# Armor_Plate.net
KiCad netlist of a schematic drawn in Altium Designer
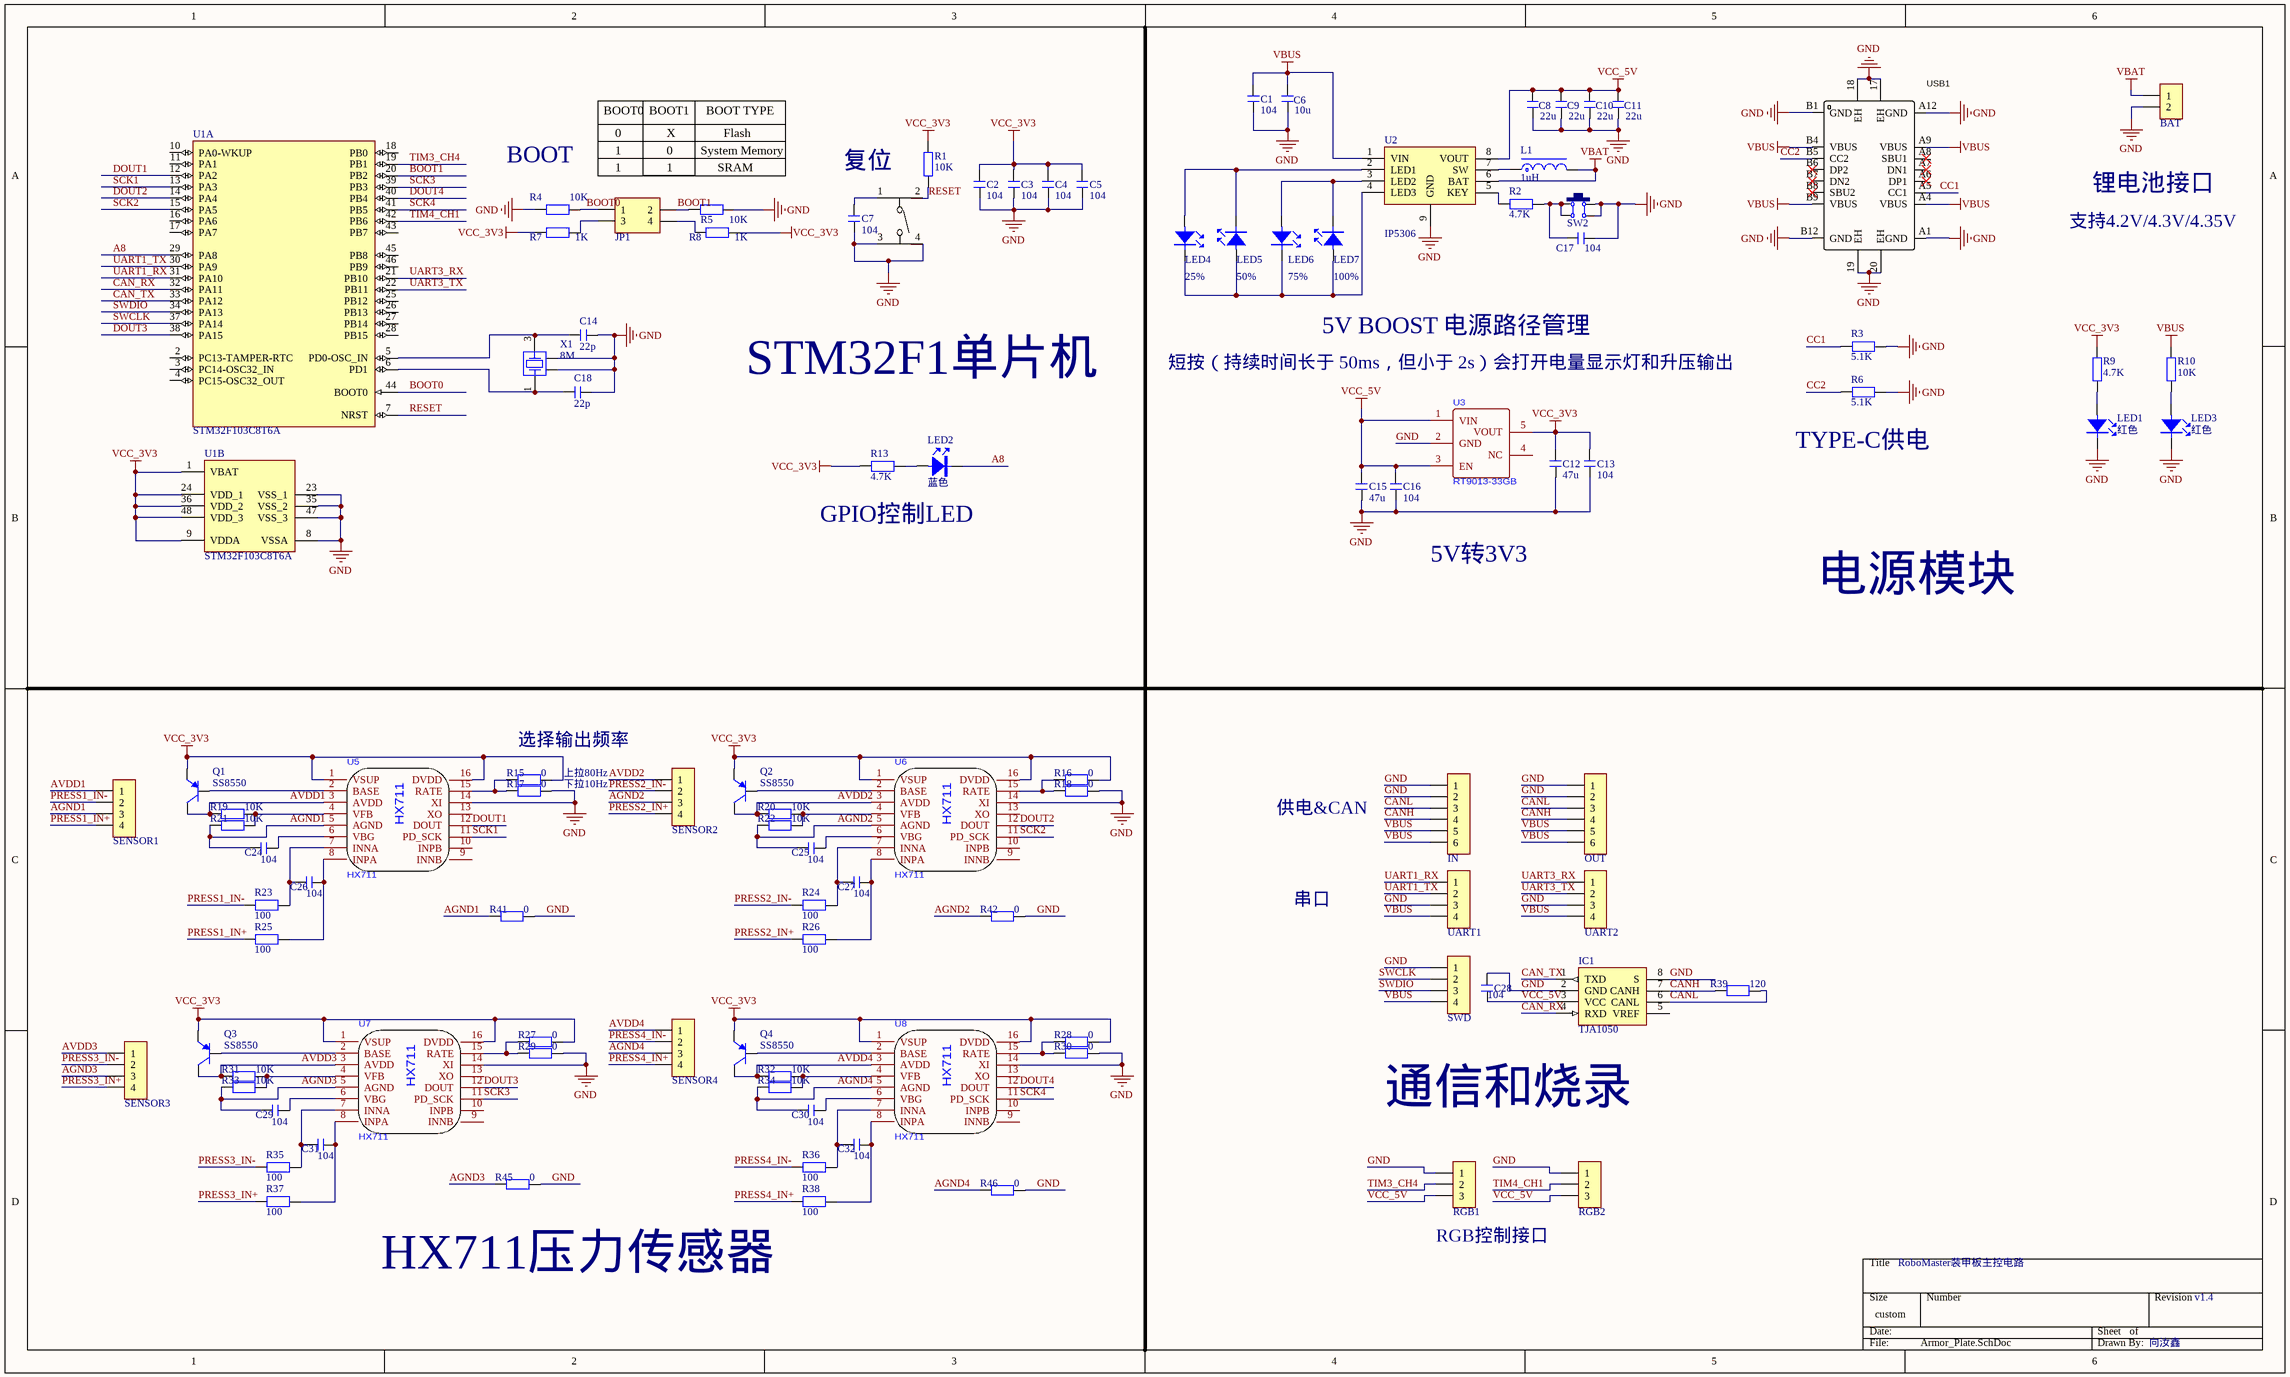
[diagram p0: Armor_Plate.SchDoc]

(export (version "E")
  (design (tool "Eeschema 10.0.6"))
  (components
    (comp (ref "BAT")
      (value "HDR-1X2")
      (footprint "XH2.54-WS-2P")
      (description "2P接插件")
      (libsource (lib "18 - 接插件-脚距2.54mm (100mil) ") (part "Header 2"))
    )
    (comp (ref "C1")
      (value "104")
      (footprint "C 0603_L")
      (description "贴片电容")
      (libsource (lib "01 - 电容-电阻-电感") (part "C"))
    )
    (comp (ref "C2")
      (value "104")
      (footprint "C 0603_L")
      (description "贴片电容")
      (libsource (lib "01 - 电容-电阻-电感") (part "C"))
    )
    (comp (ref "C3")
      (value "104")
      (footprint "C 0603_L")
      (description "贴片电容")
      (libsource (lib "01 - 电容-电阻-电感") (part "C"))
    )
    (comp (ref "C4")
      (value "104")
      (footprint "C 0603_L")
      (description "贴片电容")
      (libsource (lib "01 - 电容-电阻-电感") (part "C"))
    )
    (comp (ref "C5")
      (value "104")
      (footprint "C 0603_L")
      (description "贴片电容")
      (libsource (lib "01 - 电容-电阻-电感") (part "C"))
    )
    (comp (ref "C6")
      (value "10u")
      (footprint "C 0603_L")
      (description "贴片电容")
      (libsource (lib "01 - 电容-电阻-电感") (part "C"))
    )
    (comp (ref "C7")
      (value "104")
      (footprint "C 0603_L")
      (description "贴片电容")
      (libsource (lib "01 - 电容-电阻-电感") (part "C"))
    )
    (comp (ref "C8")
      (value "22u")
      (footprint "C 0603_L")
      (description "贴片电容")
      (libsource (lib "01 - 电容-电阻-电感") (part "C"))
    )
    (comp (ref "C9")
      (value "22u")
      (footprint "C 0603_L")
      (description "贴片电容")
      (libsource (lib "01 - 电容-电阻-电感") (part "C"))
    )
    (comp (ref "C10")
      (value "22u")
      (footprint "C 0603_L")
      (description "贴片电容")
      (libsource (lib "01 - 电容-电阻-电感") (part "C"))
    )
    (comp (ref "C11")
      (value "22u")
      (footprint "C 0603_L")
      (description "贴片电容")
      (libsource (lib "01 - 电容-电阻-电感") (part "C"))
    )
    (comp (ref "C12")
      (value "47u")
      (footprint "C 0805_L")
      (description "贴片电容")
      (libsource (lib "01 - 电容-电阻-电感") (part "C"))
    )
    (comp (ref "C13")
      (value "104")
      (footprint "C 0805_L")
      (description "贴片电容")
      (libsource (lib "01 - 电容-电阻-电感") (part "C"))
    )
    (comp (ref "C14")
      (value "22p")
      (footprint "C 0603_L")
      (description "贴片电容")
      (libsource (lib "01 - 电容-电阻-电感") (part "C"))
    )
    (comp (ref "C15")
      (value "47u")
      (footprint "C 0805_L")
      (description "贴片电容")
      (libsource (lib "01 - 电容-电阻-电感") (part "C"))
    )
    (comp (ref "C16")
      (value "104")
      (footprint "C 0805_L")
      (description "贴片电容")
      (libsource (lib "01 - 电容-电阻-电感") (part "C"))
    )
    (comp (ref "C17")
      (value "104")
      (footprint "C 0603_L")
      (description "贴片电容")
      (libsource (lib "01 - 电容-电阻-电感") (part "C"))
    )
    (comp (ref "C18")
      (value "22p")
      (footprint "C 0603_L")
      (description "贴片电容")
      (libsource (lib "01 - 电容-电阻-电感") (part "C"))
    )
    (comp (ref "C24")
      (value "104")
      (footprint "C 0603_L")
      (description "贴片电容")
      (libsource (lib "01 - 电容-电阻-电感") (part "C"))
    )
    (comp (ref "C25")
      (value "104")
      (footprint "C 0603_L")
      (description "贴片电容")
      (libsource (lib "01 - 电容-电阻-电感") (part "C"))
    )
    (comp (ref "C26")
      (value "104")
      (footprint "C 0603_L")
      (description "贴片电容")
      (libsource (lib "01 - 电容-电阻-电感") (part "C"))
    )
    (comp (ref "C27")
      (value "104")
      (footprint "C 0603_L")
      (description "贴片电容")
      (libsource (lib "01 - 电容-电阻-电感") (part "C"))
    )
    (comp (ref "C28")
      (value "104")
      (footprint "C 0603_L")
      (description "贴片电容")
      (libsource (lib "01 - 电容-电阻-电感") (part "C"))
    )
    (comp (ref "C29")
      (value "104")
      (footprint "C 0603_L")
      (description "贴片电容")
      (libsource (lib "01 - 电容-电阻-电感") (part "C"))
    )
    (comp (ref "C30")
      (value "104")
      (footprint "C 0603_L")
      (description "贴片电容")
      (libsource (lib "01 - 电容-电阻-电感") (part "C"))
    )
    (comp (ref "C31")
      (value "104")
      (footprint "C 0603_L")
      (description "贴片电容")
      (libsource (lib "01 - 电容-电阻-电感") (part "C"))
    )
    (comp (ref "C32")
      (value "104")
      (footprint "C 0603_L")
      (description "贴片电容")
      (libsource (lib "01 - 电容-电阻-电感") (part "C"))
    )
    (comp (ref "IC1")
      (value "TJA1050")
      (footprint "SOP8_N")
      (description "CAN总线收发芯片")
      (libsource (lib "39 - 其他芯片类") (part "TJA1050"))
    )
    (comp (ref "IN")
      (value "HDR-1X6")
      (footprint "GH1.25-WS-6P")
      (description "6P接插件")
      (libsource (lib "14 - 接插件-脚距1.25mm") (part "Header 6"))
    )
    (comp (ref "JP1")
      (value "Header2X2")
      (footprint "HDR2.54-LI-2x2P")
      (description "2*2P接插件")
      (libsource (lib "18 - 接插件-脚距2.54mm (100mil) ") (part "Header 2X2"))
    )
    (comp (ref "L1")
      (value "1uH")
      (footprint "CD31")
      (description "CD系列贴片线绕功率电感")
      (libsource (lib "01 - 电容-电阻-电感") (part "L-SMD"))
    )
    (comp (ref "LED1")
      (value "红色")
      (footprint "LED 0805R")
      (description "贴片LED")
      (libsource (lib "02 - 二极管(LED)-三极管-整流桥") (part "LED-SMD"))
    )
    (comp (ref "LED2")
      (value "蓝色")
      (footprint "LED 0805B")
      (description "贴片LED")
      (libsource (lib "02 - 二极管(LED)-三极管-整流桥") (part "LED-SMD"))
    )
    (comp (ref "LED3")
      (value "红色")
      (footprint "LED 0805R")
      (description "贴片LED")
      (libsource (lib "02 - 二极管(LED)-三极管-整流桥") (part "LED-SMD"))
    )
    (comp (ref "LED4")
      (value "25%")
      (footprint "LED 0603G")
      (description "贴片LED")
      (libsource (lib "02 - 二极管(LED)-三极管-整流桥") (part "LED-SMD"))
    )
    (comp (ref "LED5")
      (value "50%")
      (footprint "LED 0603G")
      (description "贴片LED")
      (libsource (lib "02 - 二极管(LED)-三极管-整流桥") (part "LED-SMD"))
    )
    (comp (ref "LED6")
      (value "75%")
      (footprint "LED 0603G")
      (description "贴片LED")
      (libsource (lib "02 - 二极管(LED)-三极管-整流桥") (part "LED-SMD"))
    )
    (comp (ref "LED7")
      (value "100%")
      (footprint "LED 0603G")
      (description "贴片LED")
      (libsource (lib "02 - 二极管(LED)-三极管-整流桥") (part "LED-SMD"))
    )
    (comp (ref "OUT")
      (value "HDR-1X6")
      (footprint "GH1.25-WS-6P")
      (description "6P接插件")
      (libsource (lib "14 - 接插件-脚距1.25mm") (part "Header 6"))
    )
    (comp (ref "Q1")
      (value "SS8550")
      (footprint "SOT23-3N")
      (description "高频放大-PNP型")
      (libsource (lib "02 - 二极管(LED)-三极管-整流桥") (part "8550-SMD"))
    )
    (comp (ref "Q2")
      (value "SS8550")
      (footprint "SOT23-3N")
      (description "高频放大-PNP型")
      (libsource (lib "02 - 二极管(LED)-三极管-整流桥") (part "8550-SMD"))
    )
    (comp (ref "Q3")
      (value "SS8550")
      (footprint "SOT23-3N")
      (description "高频放大-PNP型")
      (libsource (lib "02 - 二极管(LED)-三极管-整流桥") (part "8550-SMD"))
    )
    (comp (ref "Q4")
      (value "SS8550")
      (footprint "SOT23-3N")
      (description "高频放大-PNP型")
      (libsource (lib "02 - 二极管(LED)-三极管-整流桥") (part "8550-SMD"))
    )
    (comp (ref "R1")
      (value "10K")
      (footprint "R 0603_L")
      (description "贴片电阻")
      (libsource (lib "01 - 电容-电阻-电感") (part "R"))
    )
    (comp (ref "R2")
      (value "4.7K")
      (footprint "R 0603_L")
      (description "贴片电阻")
      (libsource (lib "01 - 电容-电阻-电感") (part "R"))
    )
    (comp (ref "R3")
      (value "5.1K")
      (footprint "R 0603_L")
      (description "贴片电阻")
      (libsource (lib "01 - 电容-电阻-电感") (part "R"))
    )
    (comp (ref "R4")
      (value "10K")
      (footprint "R 0603_L")
      (description "贴片电阻")
      (libsource (lib "01 - 电容-电阻-电感") (part "R"))
    )
    (comp (ref "R5")
      (value "10K")
      (footprint "R 0603_L")
      (description "贴片电阻")
      (libsource (lib "01 - 电容-电阻-电感") (part "R"))
    )
    (comp (ref "R6")
      (value "5.1K")
      (footprint "R 0603_L")
      (description "贴片电阻")
      (libsource (lib "01 - 电容-电阻-电感") (part "R"))
    )
    (comp (ref "R7")
      (value "1K")
      (footprint "R 0603_L")
      (description "贴片电阻")
      (libsource (lib "01 - 电容-电阻-电感") (part "R"))
    )
    (comp (ref "R8")
      (value "1K")
      (footprint "R 0603_L")
      (description "贴片电阻")
      (libsource (lib "01 - 电容-电阻-电感") (part "R"))
    )
    (comp (ref "R9")
      (value "4.7K")
      (footprint "R 0603_L")
      (description "贴片电阻")
      (libsource (lib "01 - 电容-电阻-电感") (part "R"))
    )
    (comp (ref "R10")
      (value "10K")
      (footprint "R 0603_L")
      (description "贴片电阻")
      (libsource (lib "01 - 电容-电阻-电感") (part "R"))
    )
    (comp (ref "R13")
      (value "4.7K")
      (footprint "R 0603_L")
      (description "贴片电阻")
      (libsource (lib "01 - 电容-电阻-电感") (part "R"))
    )
    (comp (ref "R15")
      (value "0")
      (footprint "R 0603_L")
      (description "贴片电阻")
      (libsource (lib "01 - 电容-电阻-电感") (part "R"))
    )
    (comp (ref "R16")
      (value "0")
      (footprint "R 0603_L")
      (description "贴片电阻")
      (libsource (lib "01 - 电容-电阻-电感") (part "R"))
    )
    (comp (ref "R17")
      (value "0")
      (footprint "R 0603_L")
      (description "贴片电阻")
      (libsource (lib "01 - 电容-电阻-电感") (part "R"))
    )
    (comp (ref "R18")
      (value "0")
      (footprint "R 0603_L")
      (description "贴片电阻")
      (libsource (lib "01 - 电容-电阻-电感") (part "R"))
    )
    (comp (ref "R19")
      (value "10K")
      (footprint "R 0603_L")
      (description "贴片电阻")
      (libsource (lib "01 - 电容-电阻-电感") (part "R"))
    )
    (comp (ref "R20")
      (value "10K")
      (footprint "R 0603_L")
      (description "贴片电阻")
      (libsource (lib "01 - 电容-电阻-电感") (part "R"))
    )
    (comp (ref "R21")
      (value "10K")
      (footprint "R 0603_L")
      (description "贴片电阻")
      (libsource (lib "01 - 电容-电阻-电感") (part "R"))
    )
    (comp (ref "R22")
      (value "10K")
      (footprint "R 0603_L")
      (description "贴片电阻")
      (libsource (lib "01 - 电容-电阻-电感") (part "R"))
    )
    (comp (ref "R23")
      (value "100")
      (footprint "R 0603_L")
      (description "贴片电阻")
      (libsource (lib "01 - 电容-电阻-电感") (part "R"))
    )
    (comp (ref "R24")
      (value "100")
      (footprint "R 0603_L")
      (description "贴片电阻")
      (libsource (lib "01 - 电容-电阻-电感") (part "R"))
    )
    (comp (ref "R25")
      (value "100")
      (footprint "R 0603_L")
      (description "贴片电阻")
      (libsource (lib "01 - 电容-电阻-电感") (part "R"))
    )
    (comp (ref "R26")
      (value "100")
      (footprint "R 0603_L")
      (description "贴片电阻")
      (libsource (lib "01 - 电容-电阻-电感") (part "R"))
    )
    (comp (ref "R27")
      (value "0")
      (footprint "R 0603_L")
      (description "贴片电阻")
      (libsource (lib "01 - 电容-电阻-电感") (part "R"))
    )
    (comp (ref "R28")
      (value "0")
      (footprint "R 0603_L")
      (description "贴片电阻")
      (libsource (lib "01 - 电容-电阻-电感") (part "R"))
    )
    (comp (ref "R29")
      (value "0")
      (footprint "R 0603_L")
      (description "贴片电阻")
      (libsource (lib "01 - 电容-电阻-电感") (part "R"))
    )
    (comp (ref "R30")
      (value "0")
      (footprint "R 0603_L")
      (description "贴片电阻")
      (libsource (lib "01 - 电容-电阻-电感") (part "R"))
    )
    (comp (ref "R31")
      (value "10K")
      (footprint "R 0603_L")
      (description "贴片电阻")
      (libsource (lib "01 - 电容-电阻-电感") (part "R"))
    )
    (comp (ref "R32")
      (value "10K")
      (footprint "R 0603_L")
      (description "贴片电阻")
      (libsource (lib "01 - 电容-电阻-电感") (part "R"))
    )
    (comp (ref "R33")
      (value "10K")
      (footprint "R 0603_L")
      (description "贴片电阻")
      (libsource (lib "01 - 电容-电阻-电感") (part "R"))
    )
    (comp (ref "R34")
      (value "10K")
      (footprint "R 0603_L")
      (description "贴片电阻")
      (libsource (lib "01 - 电容-电阻-电感") (part "R"))
    )
    (comp (ref "R35")
      (value "100")
      (footprint "R 0603_L")
      (description "贴片电阻")
      (libsource (lib "01 - 电容-电阻-电感") (part "R"))
    )
    (comp (ref "R36")
      (value "100")
      (footprint "R 0603_L")
      (description "贴片电阻")
      (libsource (lib "01 - 电容-电阻-电感") (part "R"))
    )
    (comp (ref "R37")
      (value "100")
      (footprint "R 0603_L")
      (description "贴片电阻")
      (libsource (lib "01 - 电容-电阻-电感") (part "R"))
    )
    (comp (ref "R38")
      (value "100")
      (footprint "R 0603_L")
      (description "贴片电阻")
      (libsource (lib "01 - 电容-电阻-电感") (part "R"))
    )
    (comp (ref "R39")
      (value "120")
      (footprint "R 0603_L")
      (description "贴片电阻")
      (libsource (lib "01 - 电容-电阻-电感") (part "R"))
    )
    (comp (ref "R41")
      (value "0")
      (footprint "R 0603_L")
      (description "贴片电阻")
      (libsource (lib "01 - 电容-电阻-电感") (part "R"))
    )
    (comp (ref "R42")
      (value "0")
      (footprint "R 0603_L")
      (description "贴片电阻")
      (libsource (lib "01 - 电容-电阻-电感") (part "R"))
    )
    (comp (ref "R45")
      (value "0")
      (footprint "R 0603_L")
      (description "贴片电阻")
      (libsource (lib "01 - 电容-电阻-电感") (part "R"))
    )
    (comp (ref "R46")
      (value "0")
      (footprint "R 0603_L")
      (description "贴片电阻")
      (libsource (lib "01 - 电容-电阻-电感") (part "R"))
    )
    (comp (ref "RGB1")
      (value "HDR-1X3")
      (footprint "GH1.25-WS-3P")
      (description "3P接插件")
      (libsource (lib "14 - 接插件-脚距1.25mm") (part "Header 3"))
    )
    (comp (ref "RGB2")
      (value "HDR-1X3")
      (footprint "GH1.25-WS-3P")
      (description "3P接插件")
      (libsource (lib "14 - 接插件-脚距1.25mm") (part "Header 3"))
    )
    (comp (ref "SENSOR1")
      (value "HDR-1X4")
      (footprint "GH1.25-WS-4P")
      (description "4P接插件")
      (libsource (lib "14 - 接插件-脚距1.25mm") (part "Header 4"))
    )
    (comp (ref "SENSOR2")
      (value "HDR-1X4")
      (footprint "GH1.25-WS-4P")
      (description "4P接插件")
      (libsource (lib "14 - 接插件-脚距1.25mm") (part "Header 4"))
    )
    (comp (ref "SENSOR3")
      (value "HDR-1X4")
      (footprint "GH1.25-WS-4P")
      (description "4P接插件")
      (libsource (lib "14 - 接插件-脚距1.25mm") (part "Header 4"))
    )
    (comp (ref "SENSOR4")
      (value "HDR-1X4")
      (footprint "GH1.25-WS-4P")
      (description "4P接插件")
      (libsource (lib "14 - 接插件-脚距1.25mm") (part "Header 4"))
    )
    (comp (ref "SW1")
      (value "ST-1188")
      (footprint "SW-SMD_4P-L4.2-W3.2-P2.15-LS5.2")
      (fields (field (name "MANUFACTURER") "RISHENG(日昇)"))
      (libsource (lib "My_SCHLIB") (part "SW-SMD_4P-L4.2-W3.2-P2.15-LS5.2"))
    )
    (comp (ref "SW2")
      (value "6x6x5")
      (footprint "TSW SMD-6*6*4.3")
      (description "贴片6x6轻触开关")
      (libsource (lib "03 - 按键-开关-晶振-蜂鸣器") (part "TSW SMD-6x6"))
    )
    (comp (ref "SWD")
      (value "HDR-1X4")
      (footprint "GH1.25-WS-4P")
      (description "4P接插件")
      (libsource (lib "14 - 接插件-脚距1.25mm") (part "Header 4"))
    )
    (comp (ref "U1")
      (value "STM32F103C8T6A")
      (footprint "LQFP48 7X7_N")
      (libsource (lib "28 - STM32系列单片机") (part "STM32F103C8T6"))
    )
    (comp (ref "U2")
      (value "IP5306")
      (footprint "SOP-8-EX")
      (description "移动电源IC")
      (libsource (lib "My_SCHLIB") (part "IP5306"))
    )
    (comp (ref "U3")
      (value "RT9013-33GB")
      (footprint "SOT-23-5_L3.0-W1.7-P0.95-LS2.8-BR")
      (libsource (lib "My_SCHLIB") (part "RT9013-33GB"))
    )
    (comp (ref "U5")
      (value "HX711")
      (footprint "SOP-16_L10.0-W3.9-P1.27-LS6.0-BL")
      (libsource (lib "My_SCHLIB") (part "HX711"))
    )
    (comp (ref "U6")
      (value "HX711")
      (footprint "SOP-16_L10.0-W3.9-P1.27-LS6.0-BL")
      (libsource (lib "My_SCHLIB") (part "HX711"))
    )
    (comp (ref "U7")
      (value "HX711")
      (footprint "SOP-16_L10.0-W3.9-P1.27-LS6.0-BL")
      (libsource (lib "My_SCHLIB") (part "HX711"))
    )
    (comp (ref "U8")
      (value "HX711")
      (footprint "SOP-16_L10.0-W3.9-P1.27-LS6.0-BL")
      (libsource (lib "My_SCHLIB") (part "HX711"))
    )
    (comp (ref "UART1")
      (value "HDR-1X4")
      (footprint "GH1.25-WS-4P")
      (description "4P接插件")
      (libsource (lib "14 - 接插件-脚距1.25mm") (part "Header 4"))
    )
    (comp (ref "UART2")
      (value "HDR-1X4")
      (footprint "GH1.25-WS-4P")
      (description "4P接插件")
      (libsource (lib "14 - 接插件-脚距1.25mm") (part "Header 4"))
    )
    (comp (ref "USB1")
      (value "~")
      (footprint "USB-C-SMD_KH-TYPE-C-16P")
      (description "USB")
      (fields
        (field (name "BOM_SUPPLIER PART") "C2798173")
        (field (name "BOM_MANUFACTURER PART") "TYPE-C-16M-005")
        (field (name "CONTRIBUTOR") "LCSC")
      )
      (libsource (lib "04 - 接口类-USB接口-网口") (part "TYPE-C-16M-005"))
    )
    (comp (ref "X1")
      (value "8M")
      (footprint "OSC 3225-4P")
      (description "4脚无源晶振")
      (libsource (lib "03 - 按键-开关-晶振-蜂鸣器") (part "XTAL-4P"))
    )
  )
  (nets
    (net (code "2") (name "/A8") (class "Default")
      (node (ref "LED2") (pin "2") (pinfunction "K_2") (pintype "passive"))
      (node (ref "U1") (pin "29") (pinfunction "PA8_29") (pintype "bidirectional"))
    )
    (net (code "3") (name "/AGND1") (class "Default")
      (node (ref "C24") (pin "2") (pinfunction "2_2") (pintype "passive"))
      (node (ref "R21") (pin "1") (pinfunction "1_1") (pintype "passive"))
      (node (ref "R41") (pin "1") (pinfunction "1_1") (pintype "passive"))
      (node (ref "SENSOR1") (pin "3") (pinfunction "3_3") (pintype "passive"))
      (node (ref "U5") (pin "5") (pinfunction "AGND_5") (pintype "passive"))
    )
    (net (code "4") (name "/AGND2") (class "Default")
      (node (ref "C25") (pin "2") (pinfunction "2_2") (pintype "passive"))
      (node (ref "R22") (pin "1") (pinfunction "1_1") (pintype "passive"))
      (node (ref "R42") (pin "1") (pinfunction "1_1") (pintype "passive"))
      (node (ref "SENSOR2") (pin "3") (pinfunction "3_3") (pintype "passive"))
      (node (ref "U6") (pin "5") (pinfunction "AGND_5") (pintype "passive"))
    )
    (net (code "5") (name "/AGND3") (class "Default")
      (node (ref "C29") (pin "2") (pinfunction "2_2") (pintype "passive"))
      (node (ref "R33") (pin "1") (pinfunction "1_1") (pintype "passive"))
      (node (ref "R45") (pin "1") (pinfunction "1_1") (pintype "passive"))
      (node (ref "SENSOR3") (pin "3") (pinfunction "3_3") (pintype "passive"))
      (node (ref "U7") (pin "5") (pinfunction "AGND_5") (pintype "passive"))
    )
    (net (code "6") (name "/AGND4") (class "Default")
      (node (ref "C30") (pin "2") (pinfunction "2_2") (pintype "passive"))
      (node (ref "R34") (pin "1") (pinfunction "1_1") (pintype "passive"))
      (node (ref "R46") (pin "1") (pinfunction "1_1") (pintype "passive"))
      (node (ref "SENSOR4") (pin "3") (pinfunction "3_3") (pintype "passive"))
      (node (ref "U8") (pin "5") (pinfunction "AGND_5") (pintype "passive"))
    )
    (net (code "7") (name "/AVDD1") (class "Default")
      (node (ref "Q1") (pin "3") (pinfunction "C_3") (pintype "passive"))
      (node (ref "R19") (pin "1") (pinfunction "1_1") (pintype "passive"))
      (node (ref "SENSOR1") (pin "1") (pinfunction "1_1") (pintype "passive"))
      (node (ref "U5") (pin "3") (pinfunction "AVDD_3") (pintype "passive"))
    )
    (net (code "8") (name "/AVDD2") (class "Default")
      (node (ref "Q2") (pin "3") (pinfunction "C_3") (pintype "passive"))
      (node (ref "R20") (pin "1") (pinfunction "1_1") (pintype "passive"))
      (node (ref "SENSOR2") (pin "1") (pinfunction "1_1") (pintype "passive"))
      (node (ref "U6") (pin "3") (pinfunction "AVDD_3") (pintype "passive"))
    )
    (net (code "9") (name "/AVDD3") (class "Default")
      (node (ref "Q3") (pin "3") (pinfunction "C_3") (pintype "passive"))
      (node (ref "R31") (pin "1") (pinfunction "1_1") (pintype "passive"))
      (node (ref "SENSOR3") (pin "1") (pinfunction "1_1") (pintype "passive"))
      (node (ref "U7") (pin "3") (pinfunction "AVDD_3") (pintype "passive"))
    )
    (net (code "10") (name "/AVDD4") (class "Default")
      (node (ref "Q4") (pin "3") (pinfunction "C_3") (pintype "passive"))
      (node (ref "R32") (pin "1") (pinfunction "1_1") (pintype "passive"))
      (node (ref "SENSOR4") (pin "1") (pinfunction "1_1") (pintype "passive"))
      (node (ref "U8") (pin "3") (pinfunction "AVDD_3") (pintype "passive"))
    )
    (net (code "11") (name "/BOOT0") (class "Default")
      (node (ref "JP1") (pin "1") (pinfunction "1_1") (pintype "passive"))
      (node (ref "R4") (pin "2") (pinfunction "2_2") (pintype "passive"))
      (node (ref "U1") (pin "44") (pinfunction "BOOT0_44") (pintype "input"))
    )
    (net (code "12") (name "/BOOT1") (class "Default")
      (node (ref "JP1") (pin "2") (pinfunction "2_2") (pintype "passive"))
      (node (ref "R5") (pin "1") (pinfunction "1_1") (pintype "passive"))
      (node (ref "U1") (pin "20") (pinfunction "PB2_20") (pintype "bidirectional"))
    )
    (net (code "13") (name "/CANH") (class "Default")
      (node (ref "IC1") (pin "7") (pinfunction "CANH_7") (pintype "passive"))
      (node (ref "IN") (pin "4") (pinfunction "4_4") (pintype "passive"))
      (node (ref "OUT") (pin "4") (pinfunction "4_4") (pintype "passive"))
      (node (ref "R39") (pin "1") (pinfunction "1_1") (pintype "passive"))
    )
    (net (code "14") (name "/CANL") (class "Default")
      (node (ref "IC1") (pin "6") (pinfunction "CANL_6") (pintype "passive"))
      (node (ref "IN") (pin "3") (pinfunction "3_3") (pintype "passive"))
      (node (ref "OUT") (pin "3") (pinfunction "3_3") (pintype "passive"))
      (node (ref "R39") (pin "2") (pinfunction "2_2") (pintype "passive"))
    )
    (net (code "15") (name "/CAN_RX") (class "Default")
      (node (ref "IC1") (pin "4") (pinfunction "RXD_4") (pintype "input"))
      (node (ref "U1") (pin "32") (pinfunction "PA11_32") (pintype "bidirectional"))
    )
    (net (code "16") (name "/CAN_TX") (class "Default")
      (node (ref "IC1") (pin "1") (pinfunction "TXD_1") (pintype "output"))
      (node (ref "U1") (pin "33") (pinfunction "PA12_33") (pintype "bidirectional"))
    )
    (net (code "17") (name "/CC1") (class "Default")
      (node (ref "R3") (pin "2") (pinfunction "2_2") (pintype "passive"))
      (node (ref "USB1") (pin "A5") (pinfunction "CC1_A5") (pintype "passive"))
    )
    (net (code "18") (name "/CC2") (class "Default")
      (node (ref "R6") (pin "2") (pinfunction "2_2") (pintype "passive"))
      (node (ref "USB1") (pin "B5") (pinfunction "CC2_B5") (pintype "passive"))
    )
    (net (code "19") (name "/DOUT1") (class "Default")
      (node (ref "U1") (pin "12") (pinfunction "PA2_12") (pintype "bidirectional"))
      (node (ref "U5") (pin "12") (pinfunction "DOUT_12") (pintype "passive"))
    )
    (net (code "20") (name "/DOUT2") (class "Default")
      (node (ref "U1") (pin "14") (pinfunction "PA4_14") (pintype "bidirectional"))
      (node (ref "U6") (pin "12") (pinfunction "DOUT_12") (pintype "passive"))
    )
    (net (code "21") (name "/DOUT3") (class "Default")
      (node (ref "U1") (pin "38") (pinfunction "PA15_38") (pintype "bidirectional"))
      (node (ref "U7") (pin "12") (pinfunction "DOUT_12") (pintype "passive"))
    )
    (net (code "22") (name "/DOUT4") (class "Default")
      (node (ref "U1") (pin "40") (pinfunction "PB4_40") (pintype "bidirectional"))
      (node (ref "U8") (pin "12") (pinfunction "DOUT_12") (pintype "passive"))
    )
    (net (code "23") (name "/PRESS1_IN+") (class "Default")
      (node (ref "R25") (pin "2") (pinfunction "2_2") (pintype "passive"))
      (node (ref "SENSOR1") (pin "4") (pinfunction "4_4") (pintype "passive"))
    )
    (net (code "24") (name "/PRESS1_IN-") (class "Default")
      (node (ref "R23") (pin "1") (pinfunction "1_1") (pintype "passive"))
      (node (ref "SENSOR1") (pin "2") (pinfunction "2_2") (pintype "passive"))
    )
    (net (code "25") (name "/PRESS2_IN+") (class "Default")
      (node (ref "R26") (pin "2") (pinfunction "2_2") (pintype "passive"))
      (node (ref "SENSOR2") (pin "4") (pinfunction "4_4") (pintype "passive"))
    )
    (net (code "26") (name "/PRESS2_IN-") (class "Default")
      (node (ref "R24") (pin "1") (pinfunction "1_1") (pintype "passive"))
      (node (ref "SENSOR2") (pin "2") (pinfunction "2_2") (pintype "passive"))
    )
    (net (code "27") (name "/PRESS3_IN+") (class "Default")
      (node (ref "R37") (pin "2") (pinfunction "2_2") (pintype "passive"))
      (node (ref "SENSOR3") (pin "4") (pinfunction "4_4") (pintype "passive"))
    )
    (net (code "28") (name "/PRESS3_IN-") (class "Default")
      (node (ref "R35") (pin "1") (pinfunction "1_1") (pintype "passive"))
      (node (ref "SENSOR3") (pin "2") (pinfunction "2_2") (pintype "passive"))
    )
    (net (code "29") (name "/PRESS4_IN+") (class "Default")
      (node (ref "R38") (pin "2") (pinfunction "2_2") (pintype "passive"))
      (node (ref "SENSOR4") (pin "4") (pinfunction "4_4") (pintype "passive"))
    )
    (net (code "30") (name "/PRESS4_IN-") (class "Default")
      (node (ref "R36") (pin "1") (pinfunction "1_1") (pintype "passive"))
      (node (ref "SENSOR4") (pin "2") (pinfunction "2_2") (pintype "passive"))
    )
    (net (code "31") (name "/RESET") (class "Default")
      (node (ref "R1") (pin "1") (pinfunction "1_1") (pintype "passive"))
      (node (ref "SW1") (pin "2") (pinfunction "2_2") (pintype "passive"))
      (node (ref "U1") (pin "7") (pinfunction "NRST_7") (pintype "bidirectional"))
    )
    (net (code "32") (name "/SCK1") (class "Default")
      (node (ref "U1") (pin "13") (pinfunction "PA3_13") (pintype "bidirectional"))
      (node (ref "U5") (pin "11") (pinfunction "PD_SCK_11") (pintype "passive"))
    )
    (net (code "33") (name "/SCK2") (class "Default")
      (node (ref "U1") (pin "15") (pinfunction "PA5_15") (pintype "bidirectional"))
      (node (ref "U6") (pin "11") (pinfunction "PD_SCK_11") (pintype "passive"))
    )
    (net (code "34") (name "/SCK3") (class "Default")
      (node (ref "U1") (pin "39") (pinfunction "PB3_39") (pintype "bidirectional"))
      (node (ref "U7") (pin "11") (pinfunction "PD_SCK_11") (pintype "passive"))
    )
    (net (code "35") (name "/SCK4") (class "Default")
      (node (ref "U1") (pin "41") (pinfunction "PB5_41") (pintype "bidirectional"))
      (node (ref "U8") (pin "11") (pinfunction "PD_SCK_11") (pintype "passive"))
    )
    (net (code "36") (name "/SWCLK") (class "Default")
      (node (ref "SWD") (pin "2") (pinfunction "2_2") (pintype "passive"))
      (node (ref "U1") (pin "37") (pinfunction "PA14_37") (pintype "bidirectional"))
    )
    (net (code "37") (name "/SWDIO") (class "Default")
      (node (ref "SWD") (pin "3") (pinfunction "3_3") (pintype "passive"))
      (node (ref "U1") (pin "34") (pinfunction "PA13_34") (pintype "bidirectional"))
    )
    (net (code "38") (name "/TIM3_CH4") (class "Default")
      (node (ref "RGB1") (pin "2") (pinfunction "2_2") (pintype "passive"))
      (node (ref "U1") (pin "19") (pinfunction "PB1_19") (pintype "bidirectional"))
    )
    (net (code "39") (name "/TIM4_CH1") (class "Default")
      (node (ref "RGB2") (pin "2") (pinfunction "2_2") (pintype "passive"))
      (node (ref "U1") (pin "42") (pinfunction "PB6_42") (pintype "bidirectional"))
    )
    (net (code "40") (name "/UART1_RX") (class "Default")
      (node (ref "U1") (pin "31") (pinfunction "PA10_31") (pintype "bidirectional"))
      (node (ref "UART1") (pin "1") (pinfunction "1_1") (pintype "passive"))
    )
    (net (code "41") (name "/UART1_TX") (class "Default")
      (node (ref "U1") (pin "30") (pinfunction "PA9_30") (pintype "bidirectional"))
      (node (ref "UART1") (pin "2") (pinfunction "2_2") (pintype "passive"))
    )
    (net (code "42") (name "/UART3_RX") (class "Default")
      (node (ref "U1") (pin "21") (pinfunction "PB10_21") (pintype "bidirectional"))
      (node (ref "UART2") (pin "1") (pinfunction "1_1") (pintype "passive"))
    )
    (net (code "43") (name "/UART3_TX") (class "Default")
      (node (ref "U1") (pin "22") (pinfunction "PB11_22") (pintype "bidirectional"))
      (node (ref "UART2") (pin "2") (pinfunction "2_2") (pintype "passive"))
    )
    (net (code "44") (name "GND") (class "Default")
      (node (ref "BAT") (pin "2") (pinfunction "2_2") (pintype "passive"))
      (node (ref "C1") (pin "1") (pinfunction "1_1") (pintype "passive"))
      (node (ref "C10") (pin "1") (pinfunction "1_1") (pintype "passive"))
      (node (ref "C11") (pin "1") (pinfunction "1_1") (pintype "passive"))
      (node (ref "C12") (pin "1") (pinfunction "1_1") (pintype "passive"))
      (node (ref "C13") (pin "1") (pinfunction "1_1") (pintype "passive"))
      (node (ref "C14") (pin "2") (pinfunction "2_2") (pintype "passive"))
      (node (ref "C15") (pin "1") (pinfunction "1_1") (pintype "passive"))
      (node (ref "C16") (pin "1") (pinfunction "1_1") (pintype "passive"))
      (node (ref "C17") (pin "1") (pinfunction "1_1") (pintype "passive"))
      (node (ref "C18") (pin "2") (pinfunction "2_2") (pintype "passive"))
      (node (ref "C2") (pin "1") (pinfunction "1_1") (pintype "passive"))
      (node (ref "C28") (pin "2") (pinfunction "2_2") (pintype "passive"))
      (node (ref "C3") (pin "1") (pinfunction "1_1") (pintype "passive"))
      (node (ref "C4") (pin "1") (pinfunction "1_1") (pintype "passive"))
      (node (ref "C5") (pin "1") (pinfunction "1_1") (pintype "passive"))
      (node (ref "C6") (pin "1") (pinfunction "1_1") (pintype "passive"))
      (node (ref "C7") (pin "1") (pinfunction "1_1") (pintype "passive"))
      (node (ref "C8") (pin "1") (pinfunction "1_1") (pintype "passive"))
      (node (ref "C9") (pin "1") (pinfunction "1_1") (pintype "passive"))
      (node (ref "IC1") (pin "2") (pinfunction "GND_2") (pintype "passive"))
      (node (ref "IC1") (pin "8") (pinfunction "S_8") (pintype "passive"))
      (node (ref "IN") (pin "1") (pinfunction "1_1") (pintype "passive"))
      (node (ref "IN") (pin "2") (pinfunction "2_2") (pintype "passive"))
      (node (ref "LED1") (pin "2") (pinfunction "K_2") (pintype "passive"))
      (node (ref "LED3") (pin "2") (pinfunction "K_2") (pintype "passive"))
      (node (ref "OUT") (pin "1") (pinfunction "1_1") (pintype "passive"))
      (node (ref "OUT") (pin "2") (pinfunction "2_2") (pintype "passive"))
      (node (ref "R17") (pin "2") (pinfunction "2_2") (pintype "passive"))
      (node (ref "R18") (pin "2") (pinfunction "2_2") (pintype "passive"))
      (node (ref "R29") (pin "2") (pinfunction "2_2") (pintype "passive"))
      (node (ref "R3") (pin "1") (pinfunction "1_1") (pintype "passive"))
      (node (ref "R30") (pin "2") (pinfunction "2_2") (pintype "passive"))
      (node (ref "R4") (pin "1") (pinfunction "1_1") (pintype "passive"))
      (node (ref "R41") (pin "2") (pinfunction "2_2") (pintype "passive"))
      (node (ref "R42") (pin "2") (pinfunction "2_2") (pintype "passive"))
      (node (ref "R45") (pin "2") (pinfunction "2_2") (pintype "passive"))
      (node (ref "R46") (pin "2") (pinfunction "2_2") (pintype "passive"))
      (node (ref "R5") (pin "2") (pinfunction "2_2") (pintype "passive"))
      (node (ref "R6") (pin "1") (pinfunction "1_1") (pintype "passive"))
      (node (ref "RGB1") (pin "1") (pinfunction "1_1") (pintype "passive"))
      (node (ref "RGB2") (pin "1") (pinfunction "1_1") (pintype "passive"))
      (node (ref "SW1") (pin "3") (pinfunction "3_3") (pintype "passive"))
      (node (ref "SW1") (pin "4") (pinfunction "4_4") (pintype "passive"))
      (node (ref "SW2") (pin "2") (pinfunction "2_2") (pintype "passive"))
      (node (ref "SW2") (pin "3") (pinfunction "3_3") (pintype "passive"))
      (node (ref "SWD") (pin "1") (pinfunction "1_1") (pintype "passive"))
      (node (ref "U1") (pin "23") (pinfunction "VSS_1_23") (pintype "power_in"))
      (node (ref "U1") (pin "35") (pinfunction "VSS_2_35") (pintype "power_in"))
      (node (ref "U1") (pin "47") (pinfunction "VSS_3_47") (pintype "power_in"))
      (node (ref "U1") (pin "8") (pinfunction "VSSA_8") (pintype "power_in"))
      (node (ref "U2") (pin "9") (pinfunction "GND_9") (pintype "open_collector"))
      (node (ref "U3") (pin "2") (pinfunction "GND_2") (pintype "passive"))
      (node (ref "U5") (pin "14") (pinfunction "XI_14") (pintype "passive"))
      (node (ref "U6") (pin "14") (pinfunction "XI_14") (pintype "passive"))
      (node (ref "U7") (pin "14") (pinfunction "XI_14") (pintype "passive"))
      (node (ref "U8") (pin "14") (pinfunction "XI_14") (pintype "passive"))
      (node (ref "UART1") (pin "3") (pinfunction "3_3") (pintype "passive"))
      (node (ref "UART2") (pin "3") (pinfunction "3_3") (pintype "passive"))
      (node (ref "USB1") (pin "17") (pinfunction "EH_17") (pintype "passive"))
      (node (ref "USB1") (pin "18") (pinfunction "EH_18") (pintype "passive"))
      (node (ref "USB1") (pin "19") (pinfunction "EH_19") (pintype "passive"))
      (node (ref "USB1") (pin "20") (pinfunction "EH_20") (pintype "passive"))
      (node (ref "USB1") (pin "A1") (pinfunction "GND_A1") (pintype "passive"))
      (node (ref "USB1") (pin "A12") (pinfunction "GND_A12") (pintype "passive"))
      (node (ref "USB1") (pin "B1") (pinfunction "GND_B1") (pintype "passive"))
      (node (ref "USB1") (pin "B12") (pinfunction "GND_B12") (pintype "passive"))
      (node (ref "X1") (pin "2") (pinfunction "2_2") (pintype "passive"))
      (node (ref "X1") (pin "4") (pinfunction "4_4") (pintype "passive"))
    )
    (net (code "45") (name "Net-(C7-Pad2)") (class "Default")
      (node (ref "C7") (pin "2") (pinfunction "2_2") (pintype "passive"))
      (node (ref "SW1") (pin "1") (pinfunction "1_1") (pintype "passive"))
    )
    (net (code "46") (name "Net-(C17-Pad2)") (class "Default")
      (node (ref "C17") (pin "2") (pinfunction "2_2") (pintype "passive"))
      (node (ref "R2") (pin "1") (pinfunction "1_1") (pintype "passive"))
      (node (ref "SW2") (pin "1") (pinfunction "1_1") (pintype "passive"))
      (node (ref "SW2") (pin "4") (pinfunction "4_4") (pintype "passive"))
    )
    (net (code "47") (name "Net-(JP1-Pad3)") (class "Default")
      (node (ref "JP1") (pin "3") (pinfunction "3_3") (pintype "passive"))
      (node (ref "R7") (pin "2") (pinfunction "2_2") (pintype "passive"))
    )
    (net (code "48") (name "Net-(JP1-Pad4)") (class "Default")
      (node (ref "JP1") (pin "4") (pinfunction "4_4") (pintype "passive"))
      (node (ref "R8") (pin "1") (pinfunction "1_1") (pintype "passive"))
    )
    (net (code "49") (name "Net-(LED1-A)") (class "Default")
      (node (ref "LED1") (pin "1") (pinfunction "A_1") (pintype "passive"))
      (node (ref "R9") (pin "1") (pinfunction "1_1") (pintype "passive"))
    )
    (net (code "50") (name "Net-(LED2-A)") (class "Default")
      (node (ref "LED2") (pin "1") (pinfunction "A_1") (pintype "passive"))
      (node (ref "R13") (pin "2") (pinfunction "2_2") (pintype "passive"))
    )
    (net (code "51") (name "Net-(LED3-A)") (class "Default")
      (node (ref "LED3") (pin "1") (pinfunction "A_1") (pintype "passive"))
      (node (ref "R10") (pin "1") (pinfunction "1_1") (pintype "passive"))
    )
    (net (code "52") (name "Net-(LED4-A)") (class "Default")
      (node (ref "LED4") (pin "1") (pinfunction "A_1") (pintype "passive"))
      (node (ref "LED5") (pin "2") (pinfunction "K_2") (pintype "passive"))
      (node (ref "U2") (pin "2") (pinfunction "LED1_2") (pintype "open_collector"))
    )
    (net (code "53") (name "Net-(LED4-K)") (class "Default")
      (node (ref "LED4") (pin "2") (pinfunction "K_2") (pintype "passive"))
      (node (ref "LED5") (pin "1") (pinfunction "A_1") (pintype "passive"))
      (node (ref "LED6") (pin "2") (pinfunction "K_2") (pintype "passive"))
      (node (ref "LED7") (pin "1") (pinfunction "A_1") (pintype "passive"))
      (node (ref "U2") (pin "4") (pinfunction "LED3_4") (pintype "open_collector"))
    )
    (net (code "54") (name "Net-(LED6-A)") (class "Default")
      (node (ref "LED6") (pin "1") (pinfunction "A_1") (pintype "passive"))
      (node (ref "LED7") (pin "2") (pinfunction "K_2") (pintype "passive"))
      (node (ref "U2") (pin "3") (pinfunction "LED2_3") (pintype "open_collector"))
    )
    (net (code "55") (name "Net-(Q1-B)") (class "Default")
      (node (ref "Q1") (pin "1") (pinfunction "B_1") (pintype "passive"))
      (node (ref "U5") (pin "2") (pinfunction "BASE_2") (pintype "passive"))
    )
    (net (code "56") (name "Net-(Q2-B)") (class "Default")
      (node (ref "Q2") (pin "1") (pinfunction "B_1") (pintype "passive"))
      (node (ref "U6") (pin "2") (pinfunction "BASE_2") (pintype "passive"))
    )
    (net (code "57") (name "Net-(Q3-B)") (class "Default")
      (node (ref "Q3") (pin "1") (pinfunction "B_1") (pintype "passive"))
      (node (ref "U7") (pin "2") (pinfunction "BASE_2") (pintype "passive"))
    )
    (net (code "58") (name "Net-(Q4-B)") (class "Default")
      (node (ref "Q4") (pin "1") (pinfunction "B_1") (pintype "passive"))
      (node (ref "U8") (pin "2") (pinfunction "BASE_2") (pintype "passive"))
    )
    (net (code "59") (name "Net-(U1A-PD0-OSC_IN)") (class "Default")
      (node (ref "C14") (pin "1") (pinfunction "1_1") (pintype "passive"))
      (node (ref "U1") (pin "5") (pinfunction "PD0-OSC_IN_5") (pintype "bidirectional"))
      (node (ref "X1") (pin "3") (pinfunction "3_3") (pintype "passive"))
    )
    (net (code "60") (name "Net-(U1A-PD1)") (class "Default")
      (node (ref "C18") (pin "1") (pinfunction "1_1") (pintype "passive"))
      (node (ref "U1") (pin "6") (pinfunction "PD1_6") (pintype "bidirectional"))
      (node (ref "X1") (pin "1") (pinfunction "1_1") (pintype "passive"))
    )
    (net (code "61") (name "Net-(U2-KEY)") (class "Default")
      (node (ref "R2") (pin "2") (pinfunction "2_2") (pintype "passive"))
      (node (ref "U2") (pin "5") (pinfunction "KEY_5") (pintype "open_collector"))
    )
    (net (code "62") (name "Net-(U2-SW)") (class "Default")
      (node (ref "L1") (pin "1") (pinfunction "1_1") (pintype "passive"))
      (node (ref "U2") (pin "7") (pinfunction "SW_7") (pintype "open_collector"))
    )
    (net (code "63") (name "Net-(U5-INNA)") (class "Default")
      (node (ref "C26") (pin "2") (pinfunction "2_2") (pintype "passive"))
      (node (ref "R23") (pin "2") (pinfunction "2_2") (pintype "passive"))
      (node (ref "U5") (pin "7") (pinfunction "INNA_7") (pintype "passive"))
    )
    (net (code "64") (name "Net-(U5-INPA)") (class "Default")
      (node (ref "C26") (pin "1") (pinfunction "1_1") (pintype "passive"))
      (node (ref "R25") (pin "1") (pinfunction "1_1") (pintype "passive"))
      (node (ref "U5") (pin "8") (pinfunction "INPA_8") (pintype "passive"))
    )
    (net (code "65") (name "Net-(U5-RATE)") (class "Default")
      (node (ref "R15") (pin "1") (pinfunction "1_1") (pintype "passive"))
      (node (ref "R17") (pin "1") (pinfunction "1_1") (pintype "passive"))
      (node (ref "U5") (pin "15") (pinfunction "RATE_15") (pintype "passive"))
    )
    (net (code "66") (name "Net-(U5-VBG)") (class "Default")
      (node (ref "C24") (pin "1") (pinfunction "1_1") (pintype "passive"))
      (node (ref "U5") (pin "6") (pinfunction "VBG_6") (pintype "passive"))
    )
    (net (code "67") (name "Net-(U5-VFB)") (class "Default")
      (node (ref "R19") (pin "2") (pinfunction "2_2") (pintype "passive"))
      (node (ref "R21") (pin "2") (pinfunction "2_2") (pintype "passive"))
      (node (ref "U5") (pin "4") (pinfunction "VFB_4") (pintype "passive"))
    )
    (net (code "68") (name "Net-(U6-INNA)") (class "Default")
      (node (ref "C27") (pin "2") (pinfunction "2_2") (pintype "passive"))
      (node (ref "R24") (pin "2") (pinfunction "2_2") (pintype "passive"))
      (node (ref "U6") (pin "7") (pinfunction "INNA_7") (pintype "passive"))
    )
    (net (code "69") (name "Net-(U6-INPA)") (class "Default")
      (node (ref "C27") (pin "1") (pinfunction "1_1") (pintype "passive"))
      (node (ref "R26") (pin "1") (pinfunction "1_1") (pintype "passive"))
      (node (ref "U6") (pin "8") (pinfunction "INPA_8") (pintype "passive"))
    )
    (net (code "70") (name "Net-(U6-RATE)") (class "Default")
      (node (ref "R16") (pin "1") (pinfunction "1_1") (pintype "passive"))
      (node (ref "R18") (pin "1") (pinfunction "1_1") (pintype "passive"))
      (node (ref "U6") (pin "15") (pinfunction "RATE_15") (pintype "passive"))
    )
    (net (code "71") (name "Net-(U6-VBG)") (class "Default")
      (node (ref "C25") (pin "1") (pinfunction "1_1") (pintype "passive"))
      (node (ref "U6") (pin "6") (pinfunction "VBG_6") (pintype "passive"))
    )
    (net (code "72") (name "Net-(U6-VFB)") (class "Default")
      (node (ref "R20") (pin "2") (pinfunction "2_2") (pintype "passive"))
      (node (ref "R22") (pin "2") (pinfunction "2_2") (pintype "passive"))
      (node (ref "U6") (pin "4") (pinfunction "VFB_4") (pintype "passive"))
    )
    (net (code "73") (name "Net-(U7-INNA)") (class "Default")
      (node (ref "C31") (pin "2") (pinfunction "2_2") (pintype "passive"))
      (node (ref "R35") (pin "2") (pinfunction "2_2") (pintype "passive"))
      (node (ref "U7") (pin "7") (pinfunction "INNA_7") (pintype "passive"))
    )
    (net (code "74") (name "Net-(U7-INPA)") (class "Default")
      (node (ref "C31") (pin "1") (pinfunction "1_1") (pintype "passive"))
      (node (ref "R37") (pin "1") (pinfunction "1_1") (pintype "passive"))
      (node (ref "U7") (pin "8") (pinfunction "INPA_8") (pintype "passive"))
    )
    (net (code "75") (name "Net-(U7-RATE)") (class "Default")
      (node (ref "R27") (pin "1") (pinfunction "1_1") (pintype "passive"))
      (node (ref "R29") (pin "1") (pinfunction "1_1") (pintype "passive"))
      (node (ref "U7") (pin "15") (pinfunction "RATE_15") (pintype "passive"))
    )
    (net (code "76") (name "Net-(U7-VBG)") (class "Default")
      (node (ref "C29") (pin "1") (pinfunction "1_1") (pintype "passive"))
      (node (ref "U7") (pin "6") (pinfunction "VBG_6") (pintype "passive"))
    )
    (net (code "77") (name "Net-(U7-VFB)") (class "Default")
      (node (ref "R31") (pin "2") (pinfunction "2_2") (pintype "passive"))
      (node (ref "R33") (pin "2") (pinfunction "2_2") (pintype "passive"))
      (node (ref "U7") (pin "4") (pinfunction "VFB_4") (pintype "passive"))
    )
    (net (code "78") (name "Net-(U8-INNA)") (class "Default")
      (node (ref "C32") (pin "2") (pinfunction "2_2") (pintype "passive"))
      (node (ref "R36") (pin "2") (pinfunction "2_2") (pintype "passive"))
      (node (ref "U8") (pin "7") (pinfunction "INNA_7") (pintype "passive"))
    )
    (net (code "79") (name "Net-(U8-INPA)") (class "Default")
      (node (ref "C32") (pin "1") (pinfunction "1_1") (pintype "passive"))
      (node (ref "R38") (pin "1") (pinfunction "1_1") (pintype "passive"))
      (node (ref "U8") (pin "8") (pinfunction "INPA_8") (pintype "passive"))
    )
    (net (code "80") (name "Net-(U8-RATE)") (class "Default")
      (node (ref "R28") (pin "1") (pinfunction "1_1") (pintype "passive"))
      (node (ref "R30") (pin "1") (pinfunction "1_1") (pintype "passive"))
      (node (ref "U8") (pin "15") (pinfunction "RATE_15") (pintype "passive"))
    )
    (net (code "81") (name "Net-(U8-VBG)") (class "Default")
      (node (ref "C30") (pin "1") (pinfunction "1_1") (pintype "passive"))
      (node (ref "U8") (pin "6") (pinfunction "VBG_6") (pintype "passive"))
    )
    (net (code "82") (name "Net-(U8-VFB)") (class "Default")
      (node (ref "R32") (pin "2") (pinfunction "2_2") (pintype "passive"))
      (node (ref "R34") (pin "2") (pinfunction "2_2") (pintype "passive"))
      (node (ref "U8") (pin "4") (pinfunction "VFB_4") (pintype "passive"))
    )
    (net (code "83") (name "VBAT") (class "Default")
      (node (ref "BAT") (pin "1") (pinfunction "1_1") (pintype "passive"))
      (node (ref "L1") (pin "2") (pinfunction "2_2") (pintype "passive"))
      (node (ref "U2") (pin "6") (pinfunction "BAT_6") (pintype "open_collector"))
    )
    (net (code "84") (name "VBUS") (class "Default")
      (node (ref "C1") (pin "2") (pinfunction "2_2") (pintype "passive"))
      (node (ref "C6") (pin "2") (pinfunction "2_2") (pintype "passive"))
      (node (ref "IN") (pin "5") (pinfunction "5_5") (pintype "passive"))
      (node (ref "IN") (pin "6") (pinfunction "6_6") (pintype "passive"))
      (node (ref "OUT") (pin "5") (pinfunction "5_5") (pintype "passive"))
      (node (ref "OUT") (pin "6") (pinfunction "6_6") (pintype "passive"))
      (node (ref "R10") (pin "2") (pinfunction "2_2") (pintype "passive"))
      (node (ref "SWD") (pin "4") (pinfunction "4_4") (pintype "passive"))
      (node (ref "U2") (pin "1") (pinfunction "VIN_1") (pintype "open_collector"))
      (node (ref "UART1") (pin "4") (pinfunction "4_4") (pintype "passive"))
      (node (ref "UART2") (pin "4") (pinfunction "4_4") (pintype "passive"))
      (node (ref "USB1") (pin "A4") (pinfunction "VBUS_A4") (pintype "passive"))
      (node (ref "USB1") (pin "A9") (pinfunction "VBUS_A9") (pintype "passive"))
      (node (ref "USB1") (pin "B4") (pinfunction "VBUS_B4") (pintype "passive"))
      (node (ref "USB1") (pin "B9") (pinfunction "VBUS_B9") (pintype "passive"))
    )
    (net (code "85") (name "VCC_3V3") (class "Default")
      (node (ref "C12") (pin "2") (pinfunction "2_2") (pintype "passive"))
      (node (ref "C13") (pin "2") (pinfunction "2_2") (pintype "passive"))
      (node (ref "C2") (pin "2") (pinfunction "2_2") (pintype "passive"))
      (node (ref "C3") (pin "2") (pinfunction "2_2") (pintype "passive"))
      (node (ref "C4") (pin "2") (pinfunction "2_2") (pintype "passive"))
      (node (ref "C5") (pin "2") (pinfunction "2_2") (pintype "passive"))
      (node (ref "Q1") (pin "2") (pinfunction "E_2") (pintype "passive"))
      (node (ref "Q2") (pin "2") (pinfunction "E_2") (pintype "passive"))
      (node (ref "Q3") (pin "2") (pinfunction "E_2") (pintype "passive"))
      (node (ref "Q4") (pin "2") (pinfunction "E_2") (pintype "passive"))
      (node (ref "R1") (pin "2") (pinfunction "2_2") (pintype "passive"))
      (node (ref "R13") (pin "1") (pinfunction "1_1") (pintype "passive"))
      (node (ref "R15") (pin "2") (pinfunction "2_2") (pintype "passive"))
      (node (ref "R16") (pin "2") (pinfunction "2_2") (pintype "passive"))
      (node (ref "R27") (pin "2") (pinfunction "2_2") (pintype "passive"))
      (node (ref "R28") (pin "2") (pinfunction "2_2") (pintype "passive"))
      (node (ref "R7") (pin "1") (pinfunction "1_1") (pintype "passive"))
      (node (ref "R8") (pin "2") (pinfunction "2_2") (pintype "passive"))
      (node (ref "R9") (pin "2") (pinfunction "2_2") (pintype "passive"))
      (node (ref "U1") (pin "1") (pinfunction "VBAT_1") (pintype "power_in"))
      (node (ref "U1") (pin "24") (pinfunction "VDD_1_24") (pintype "power_in"))
      (node (ref "U1") (pin "36") (pinfunction "VDD_2_36") (pintype "power_in"))
      (node (ref "U1") (pin "48") (pinfunction "VDD_3_48") (pintype "power_in"))
      (node (ref "U1") (pin "9") (pinfunction "VDDA_9") (pintype "power_in"))
      (node (ref "U3") (pin "5") (pinfunction "VOUT_5") (pintype "passive"))
      (node (ref "U5") (pin "1") (pinfunction "VSUP_1") (pintype "passive"))
      (node (ref "U5") (pin "16") (pinfunction "DVDD_16") (pintype "passive"))
      (node (ref "U6") (pin "1") (pinfunction "VSUP_1") (pintype "passive"))
      (node (ref "U6") (pin "16") (pinfunction "DVDD_16") (pintype "passive"))
      (node (ref "U7") (pin "1") (pinfunction "VSUP_1") (pintype "passive"))
      (node (ref "U7") (pin "16") (pinfunction "DVDD_16") (pintype "passive"))
      (node (ref "U8") (pin "1") (pinfunction "VSUP_1") (pintype "passive"))
      (node (ref "U8") (pin "16") (pinfunction "DVDD_16") (pintype "passive"))
    )
    (net (code "86") (name "VCC_5V") (class "Default")
      (node (ref "C10") (pin "2") (pinfunction "2_2") (pintype "passive"))
      (node (ref "C11") (pin "2") (pinfunction "2_2") (pintype "passive"))
      (node (ref "C15") (pin "2") (pinfunction "2_2") (pintype "passive"))
      (node (ref "C16") (pin "2") (pinfunction "2_2") (pintype "passive"))
      (node (ref "C28") (pin "1") (pinfunction "1_1") (pintype "passive"))
      (node (ref "C8") (pin "2") (pinfunction "2_2") (pintype "passive"))
      (node (ref "C9") (pin "2") (pinfunction "2_2") (pintype "passive"))
      (node (ref "IC1") (pin "3") (pinfunction "VCC_3") (pintype "passive"))
      (node (ref "RGB1") (pin "3") (pinfunction "3_3") (pintype "passive"))
      (node (ref "RGB2") (pin "3") (pinfunction "3_3") (pintype "passive"))
      (node (ref "U2") (pin "8") (pinfunction "VOUT_8") (pintype "open_collector"))
      (node (ref "U3") (pin "1") (pinfunction "VIN_1") (pintype "passive"))
      (node (ref "U3") (pin "3") (pinfunction "EN_3") (pintype "passive"))
    )
    (net (code "87") (name "unconnected-(IC1-VREF-Pad5)") (class "Default")
      (node (ref "IC1") (pin "5") (pinfunction "VREF_5") (pintype "passive"))
    )
    (net (code "88") (name "unconnected-(U1A-PA0-WKUP-Pad10)") (class "Default")
      (node (ref "U1") (pin "10") (pinfunction "PA0-WKUP_10") (pintype "bidirectional"))
    )
    (net (code "89") (name "unconnected-(U1A-PA1-Pad11)") (class "Default")
      (node (ref "U1") (pin "11") (pinfunction "PA1_11") (pintype "bidirectional"))
    )
    (net (code "90") (name "unconnected-(U1A-PA6-Pad16)") (class "Default")
      (node (ref "U1") (pin "16") (pinfunction "PA6_16") (pintype "bidirectional"))
    )
    (net (code "91") (name "unconnected-(U1A-PA7-Pad17)") (class "Default")
      (node (ref "U1") (pin "17") (pinfunction "PA7_17") (pintype "bidirectional"))
    )
    (net (code "92") (name "unconnected-(U1A-PB0-Pad18)") (class "Default")
      (node (ref "U1") (pin "18") (pinfunction "PB0_18") (pintype "bidirectional"))
    )
    (net (code "93") (name "unconnected-(U1A-PB7-Pad43)") (class "Default")
      (node (ref "U1") (pin "43") (pinfunction "PB7_43") (pintype "bidirectional"))
    )
    (net (code "94") (name "unconnected-(U1A-PB8-Pad45)") (class "Default")
      (node (ref "U1") (pin "45") (pinfunction "PB8_45") (pintype "bidirectional"))
    )
    (net (code "95") (name "unconnected-(U1A-PB9-Pad46)") (class "Default")
      (node (ref "U1") (pin "46") (pinfunction "PB9_46") (pintype "bidirectional"))
    )
    (net (code "96") (name "unconnected-(U1A-PB12-Pad25)") (class "Default")
      (node (ref "U1") (pin "25") (pinfunction "PB12_25") (pintype "bidirectional"))
    )
    (net (code "97") (name "unconnected-(U1A-PB13-Pad26)") (class "Default")
      (node (ref "U1") (pin "26") (pinfunction "PB13_26") (pintype "bidirectional"))
    )
    (net (code "98") (name "unconnected-(U1A-PB14-Pad27)") (class "Default")
      (node (ref "U1") (pin "27") (pinfunction "PB14_27") (pintype "bidirectional"))
    )
    (net (code "99") (name "unconnected-(U1A-PB15-Pad28)") (class "Default")
      (node (ref "U1") (pin "28") (pinfunction "PB15_28") (pintype "bidirectional"))
    )
    (net (code "100") (name "unconnected-(U1A-PC13-TAMPER-RTC-Pad2)") (class "Default")
      (node (ref "U1") (pin "2") (pinfunction "PC13-TAMPER-RTC_2") (pintype "bidirectional"))
    )
    (net (code "101") (name "unconnected-(U1A-PC14-OSC32_IN-Pad3)") (class "Default")
      (node (ref "U1") (pin "3") (pinfunction "PC14-OSC32_IN_3") (pintype "bidirectional"))
    )
    (net (code "102") (name "unconnected-(U1A-PC15-OSC32_OUT-Pad4)") (class "Default")
      (node (ref "U1") (pin "4") (pinfunction "PC15-OSC32_OUT_4") (pintype "bidirectional"))
    )
    (net (code "103") (name "unconnected-(U3-NC-Pad4)") (class "Default")
      (node (ref "U3") (pin "4") (pinfunction "NC_4") (pintype "passive"))
    )
    (net (code "104") (name "unconnected-(U5-INNB-Pad9)") (class "Default")
      (node (ref "U5") (pin "9") (pinfunction "INNB_9") (pintype "passive"))
    )
    (net (code "105") (name "unconnected-(U5-INPB-Pad10)") (class "Default")
      (node (ref "U5") (pin "10") (pinfunction "INPB_10") (pintype "passive"))
    )
    (net (code "106") (name "unconnected-(U5-XO-Pad13)") (class "Default")
      (node (ref "U5") (pin "13") (pinfunction "XO_13") (pintype "passive"))
    )
    (net (code "107") (name "unconnected-(U6-INNB-Pad9)") (class "Default")
      (node (ref "U6") (pin "9") (pinfunction "INNB_9") (pintype "passive"))
    )
    (net (code "108") (name "unconnected-(U6-INPB-Pad10)") (class "Default")
      (node (ref "U6") (pin "10") (pinfunction "INPB_10") (pintype "passive"))
    )
    (net (code "109") (name "unconnected-(U6-XO-Pad13)") (class "Default")
      (node (ref "U6") (pin "13") (pinfunction "XO_13") (pintype "passive"))
    )
    (net (code "110") (name "unconnected-(U7-INNB-Pad9)") (class "Default")
      (node (ref "U7") (pin "9") (pinfunction "INNB_9") (pintype "passive"))
    )
    (net (code "111") (name "unconnected-(U7-INPB-Pad10)") (class "Default")
      (node (ref "U7") (pin "10") (pinfunction "INPB_10") (pintype "passive"))
    )
    (net (code "112") (name "unconnected-(U7-XO-Pad13)") (class "Default")
      (node (ref "U7") (pin "13") (pinfunction "XO_13") (pintype "passive"))
    )
    (net (code "113") (name "unconnected-(U8-INNB-Pad9)") (class "Default")
      (node (ref "U8") (pin "9") (pinfunction "INNB_9") (pintype "passive"))
    )
    (net (code "114") (name "unconnected-(U8-INPB-Pad10)") (class "Default")
      (node (ref "U8") (pin "10") (pinfunction "INPB_10") (pintype "passive"))
    )
    (net (code "115") (name "unconnected-(U8-XO-Pad13)") (class "Default")
      (node (ref "U8") (pin "13") (pinfunction "XO_13") (pintype "passive"))
    )
    (net (code "116") (name "unconnected-(USB1-DN1-PadA7)") (class "Default")
      (node (ref "USB1") (pin "A7") (pinfunction "DN1_A7") (pintype "passive+no_connect"))
    )
    (net (code "117") (name "unconnected-(USB1-DN2-PadB7)") (class "Default")
      (node (ref "USB1") (pin "B7") (pinfunction "DN2_B7") (pintype "passive+no_connect"))
    )
    (net (code "118") (name "unconnected-(USB1-DP1-PadA6)") (class "Default")
      (node (ref "USB1") (pin "A6") (pinfunction "DP1_A6") (pintype "passive+no_connect"))
    )
    (net (code "119") (name "unconnected-(USB1-DP2-PadB6)") (class "Default")
      (node (ref "USB1") (pin "B6") (pinfunction "DP2_B6") (pintype "passive+no_connect"))
    )
    (net (code "120") (name "unconnected-(USB1-SBU1-PadA8)") (class "Default")
      (node (ref "USB1") (pin "A8") (pinfunction "SBU1_A8") (pintype "passive+no_connect"))
    )
    (net (code "121") (name "unconnected-(USB1-SBU2-PadB8)") (class "Default")
      (node (ref "USB1") (pin "B8") (pinfunction "SBU2_B8") (pintype "passive+no_connect"))
    )
  )
)
